# sender.net
KiCad netlist of a schematic drawn in EAGLE
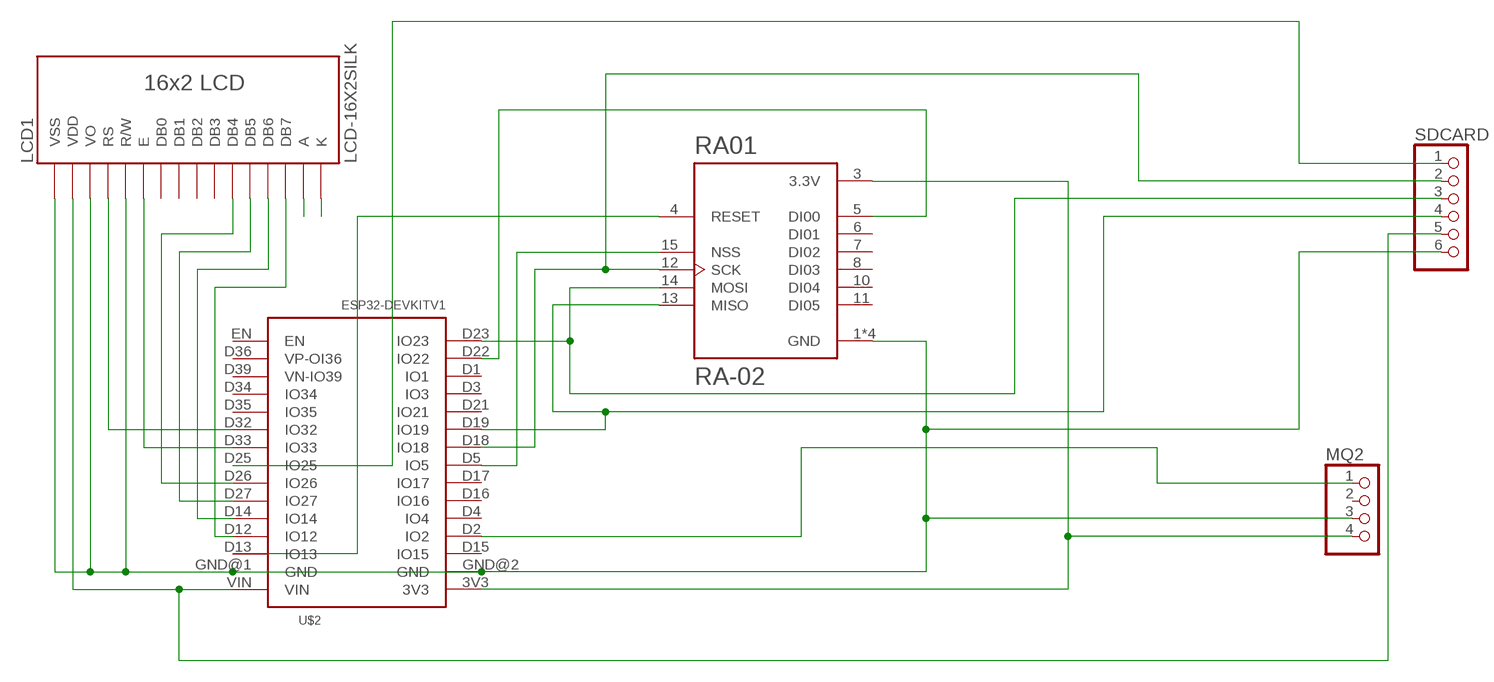
[diagram p0: schematic, sheet 1]

(export (version "E")
  (design (tool "Eeschema 10.0.6"))
  (components
    (comp (ref "LCD1")
      (value "LCD-16X2SILK")
      (footprint "eagle-import:MODULE_LCD-16X2")
      (fields (field (name "MF") "Gravitech") (field (name "MP") "LCD-16X2"))
      (libsource (lib "eagle-import") (part "LCD-16X2SILK"))
    )
    (comp (ref "MQ2")
      (value "PINHD-1X4")
      (footprint "eagle-import:1X04")
      (libsource (lib "eagle-import") (part "PINHD-1X4"))
    )
    (comp (ref "RA01")
      (value "RA-02")
      (footprint "eagle-import:RA-02")
      (fields (field (name "MF") "Ai-Thinker"))
      (libsource (lib "eagle-import") (part "RA-02"))
    )
    (comp (ref "SDCARD")
      (value "PINHD-1X6")
      (footprint "eagle-import:1X06")
      (libsource (lib "eagle-import") (part "PINHD-1X6"))
    )
    (comp (ref "U$2")
      (value "ESP32DEVKITV1")
      (footprint "eagle-import:ESP32-DEVKITV1")
      (libsource (lib "eagle-import") (part "ESP32DEVKITV1"))
    )
  )
  (nets
    (net (code "1") (name "Net-(LCD1-DB4)") (class "Default")
      (node (ref "LCD1") (pin "11") (pinfunction "DB4_11") (pintype "bidirectional"))
      (node (ref "U$2") (pin "D26") (pinfunction "IO26_D26") (pintype "bidirectional"))
    )
    (net (code "2") (name "Net-(LCD1-DB5)") (class "Default")
      (node (ref "LCD1") (pin "12") (pinfunction "DB5_12") (pintype "bidirectional"))
      (node (ref "U$2") (pin "D27") (pinfunction "IO27_D27") (pintype "bidirectional"))
    )
    (net (code "3") (name "Net-(LCD1-DB6)") (class "Default")
      (node (ref "LCD1") (pin "13") (pinfunction "DB6_13") (pintype "bidirectional"))
      (node (ref "U$2") (pin "D14") (pinfunction "IO14_D14") (pintype "bidirectional"))
    )
    (net (code "4") (name "Net-(LCD1-DB7)") (class "Default")
      (node (ref "LCD1") (pin "14") (pinfunction "DB7_14") (pintype "bidirectional"))
      (node (ref "U$2") (pin "D12") (pinfunction "IO12_D12") (pintype "bidirectional"))
    )
    (net (code "5") (name "Net-(LCD1-E)") (class "Default")
      (node (ref "LCD1") (pin "6") (pinfunction "E_6") (pintype "input"))
      (node (ref "U$2") (pin "D33") (pinfunction "IO33_D33") (pintype "bidirectional"))
    )
    (net (code "6") (name "Net-(LCD1-RS)") (class "Default")
      (node (ref "LCD1") (pin "4") (pinfunction "RS_4") (pintype "input"))
      (node (ref "U$2") (pin "D32") (pinfunction "IO32_D32") (pintype "bidirectional"))
    )
    (net (code "7") (name "Net-(LCD1-R{slash}W)") (class "Default")
      (node (ref "LCD1") (pin "1") (pinfunction "VSS_1") (pintype "power_in"))
      (node (ref "LCD1") (pin "3") (pinfunction "VO_3") (pintype "bidirectional"))
      (node (ref "LCD1") (pin "5") (pinfunction "R/W_5") (pintype "input"))
      (node (ref "MQ2") (pin "3") (pinfunction "3_3") (pintype "passive"))
      (node (ref "RA01") (pin "1") (pinfunction "GND_1") (pintype "power_in"))
      (node (ref "RA01") (pin "16") (pinfunction "GND_16") (pintype "power_in"))
      (node (ref "RA01") (pin "2") (pinfunction "GND_2") (pintype "power_in"))
      (node (ref "RA01") (pin "9") (pinfunction "GND_9") (pintype "power_in"))
      (node (ref "SDCARD") (pin "6") (pinfunction "6_6") (pintype "passive"))
      (node (ref "U$2") (pin "GND@1") (pinfunction "GND_GND@1") (pintype "bidirectional"))
      (node (ref "U$2") (pin "GND@2") (pinfunction "GND_GND@2") (pintype "bidirectional"))
    )
    (net (code "8") (name "Net-(LCD1-VDD)") (class "Default")
      (node (ref "LCD1") (pin "2") (pinfunction "VDD_2") (pintype "power_in"))
      (node (ref "SDCARD") (pin "5") (pinfunction "5_5") (pintype "passive"))
      (node (ref "U$2") (pin "VIN") (pinfunction "VIN_VIN") (pintype "bidirectional"))
    )
    (net (code "9") (name "Net-(RA01-3.3V)") (class "Default")
      (node (ref "MQ2") (pin "4") (pinfunction "4_4") (pintype "passive"))
      (node (ref "RA01") (pin "3") (pinfunction "3.3V_3") (pintype "power_in"))
      (node (ref "U$2") (pin "3V3") (pinfunction "3V3_3V3") (pintype "bidirectional"))
    )
    (net (code "10") (name "Net-(RA01-DI00)") (class "Default")
      (node (ref "RA01") (pin "5") (pinfunction "DI00_5") (pintype "bidirectional"))
      (node (ref "U$2") (pin "D22") (pinfunction "IO22_D22") (pintype "bidirectional"))
    )
    (net (code "11") (name "Net-(RA01-MISO)") (class "Default")
      (node (ref "RA01") (pin "13") (pinfunction "MISO_13") (pintype "output"))
      (node (ref "SDCARD") (pin "4") (pinfunction "4_4") (pintype "passive"))
      (node (ref "U$2") (pin "D19") (pinfunction "IO19_D19") (pintype "bidirectional"))
    )
    (net (code "12") (name "Net-(RA01-MOSI)") (class "Default")
      (node (ref "RA01") (pin "14") (pinfunction "MOSI_14") (pintype "input"))
      (node (ref "SDCARD") (pin "3") (pinfunction "3_3") (pintype "passive"))
      (node (ref "U$2") (pin "D23") (pinfunction "IO23_D23") (pintype "bidirectional"))
    )
    (net (code "13") (name "Net-(RA01-NSS)") (class "Default")
      (node (ref "RA01") (pin "15") (pinfunction "NSS_15") (pintype "input"))
      (node (ref "U$2") (pin "D5") (pinfunction "IO5_D5") (pintype "bidirectional"))
    )
    (net (code "14") (name "Net-(RA01-RESET)") (class "Default")
      (node (ref "RA01") (pin "4") (pinfunction "RESET_4") (pintype "input"))
      (node (ref "U$2") (pin "D13") (pinfunction "IO13_D13") (pintype "bidirectional"))
    )
    (net (code "15") (name "Net-(RA01-SCK)") (class "Default")
      (node (ref "RA01") (pin "12") (pinfunction "SCK_12") (pintype "input"))
      (node (ref "SDCARD") (pin "2") (pinfunction "2_2") (pintype "passive"))
      (node (ref "U$2") (pin "D18") (pinfunction "IO18_D18") (pintype "bidirectional"))
    )
    (net (code "16") (name "Net-(U$2-IO2)") (class "Default")
      (node (ref "MQ2") (pin "1") (pinfunction "1_1") (pintype "passive"))
      (node (ref "U$2") (pin "D2") (pinfunction "IO2_D2") (pintype "bidirectional"))
    )
    (net (code "17") (name "Net-(U$2-IO25)") (class "Default")
      (node (ref "SDCARD") (pin "1") (pinfunction "1_1") (pintype "passive"))
      (node (ref "U$2") (pin "D25") (pinfunction "IO25_D25") (pintype "bidirectional"))
    )
    (net (code "18") (name "unconnected-(LCD1-A-Pad15)") (class "Default")
      (node (ref "LCD1") (pin "15") (pinfunction "A_15") (pintype "power_in"))
    )
    (net (code "19") (name "unconnected-(LCD1-DB0-Pad7)") (class "Default")
      (node (ref "LCD1") (pin "7") (pinfunction "DB0_7") (pintype "bidirectional"))
    )
    (net (code "20") (name "unconnected-(LCD1-DB1-Pad8)") (class "Default")
      (node (ref "LCD1") (pin "8") (pinfunction "DB1_8") (pintype "bidirectional"))
    )
    (net (code "21") (name "unconnected-(LCD1-DB2-Pad9)") (class "Default")
      (node (ref "LCD1") (pin "9") (pinfunction "DB2_9") (pintype "bidirectional"))
    )
    (net (code "22") (name "unconnected-(LCD1-DB3-Pad10)") (class "Default")
      (node (ref "LCD1") (pin "10") (pinfunction "DB3_10") (pintype "bidirectional"))
    )
    (net (code "23") (name "unconnected-(LCD1-K-Pad16)") (class "Default")
      (node (ref "LCD1") (pin "16") (pinfunction "K_16") (pintype "power_in"))
    )
    (net (code "24") (name "unconnected-(MQ2-Pad2)") (class "Default")
      (node (ref "MQ2") (pin "2") (pinfunction "2_2") (pintype "passive"))
    )
    (net (code "25") (name "unconnected-(RA01-DI01-Pad6)") (class "Default")
      (node (ref "RA01") (pin "6") (pinfunction "DI01_6") (pintype "bidirectional"))
    )
    (net (code "26") (name "unconnected-(RA01-DI02-Pad7)") (class "Default")
      (node (ref "RA01") (pin "7") (pinfunction "DI02_7") (pintype "bidirectional"))
    )
    (net (code "27") (name "unconnected-(RA01-DI03-Pad8)") (class "Default")
      (node (ref "RA01") (pin "8") (pinfunction "DI03_8") (pintype "bidirectional"))
    )
    (net (code "28") (name "unconnected-(RA01-DI04-Pad10)") (class "Default")
      (node (ref "RA01") (pin "10") (pinfunction "DI04_10") (pintype "bidirectional"))
    )
    (net (code "29") (name "unconnected-(RA01-DI05-Pad11)") (class "Default")
      (node (ref "RA01") (pin "11") (pinfunction "DI05_11") (pintype "bidirectional"))
    )
    (net (code "30") (name "unconnected-(U$2-IO1-PadD1)") (class "Default")
      (node (ref "U$2") (pin "D1") (pinfunction "IO1_D1") (pintype "bidirectional"))
    )
    (net (code "31") (name "unconnected-(U$2-IO3-PadD3)") (class "Default")
      (node (ref "U$2") (pin "D3") (pinfunction "IO3_D3") (pintype "bidirectional"))
    )
    (net (code "32") (name "unconnected-(U$2-IO4-PadD4)") (class "Default")
      (node (ref "U$2") (pin "D4") (pinfunction "IO4_D4") (pintype "bidirectional"))
    )
    (net (code "33") (name "unconnected-(U$2-IO15-PadD15)") (class "Default")
      (node (ref "U$2") (pin "D15") (pinfunction "IO15_D15") (pintype "bidirectional"))
    )
    (net (code "34") (name "unconnected-(U$2-IO16-PadD16)") (class "Default")
      (node (ref "U$2") (pin "D16") (pinfunction "IO16_D16") (pintype "bidirectional"))
    )
    (net (code "35") (name "unconnected-(U$2-IO17-PadD17)") (class "Default")
      (node (ref "U$2") (pin "D17") (pinfunction "IO17_D17") (pintype "bidirectional"))
    )
    (net (code "36") (name "unconnected-(U$2-IO21-PadD21)") (class "Default")
      (node (ref "U$2") (pin "D21") (pinfunction "IO21_D21") (pintype "bidirectional"))
    )
    (net (code "37") (name "unconnected-(U$2-IO34-PadD34)") (class "Default")
      (node (ref "U$2") (pin "D34") (pinfunction "IO34_D34") (pintype "bidirectional"))
    )
    (net (code "38") (name "unconnected-(U$2-IO35-PadD35)") (class "Default")
      (node (ref "U$2") (pin "D35") (pinfunction "IO35_D35") (pintype "bidirectional"))
    )
    (net (code "39") (name "unconnected-(U$2-PadEN)") (class "Default")
      (node (ref "U$2") (pin "EN") (pinfunction "EN_EN") (pintype "bidirectional"))
    )
    (net (code "40") (name "unconnected-(U$2-VN-IO39-PadD39)") (class "Default")
      (node (ref "U$2") (pin "D39") (pinfunction "VN-IO39_D39") (pintype "bidirectional"))
    )
    (net (code "41") (name "unconnected-(U$2-VP-OI36-PadD36)") (class "Default")
      (node (ref "U$2") (pin "D36") (pinfunction "VP-OI36_D36") (pintype "bidirectional"))
    )
  )
)
